# CAT-897-F.net
KiCad netlist of a schematic drawn in EAGLE
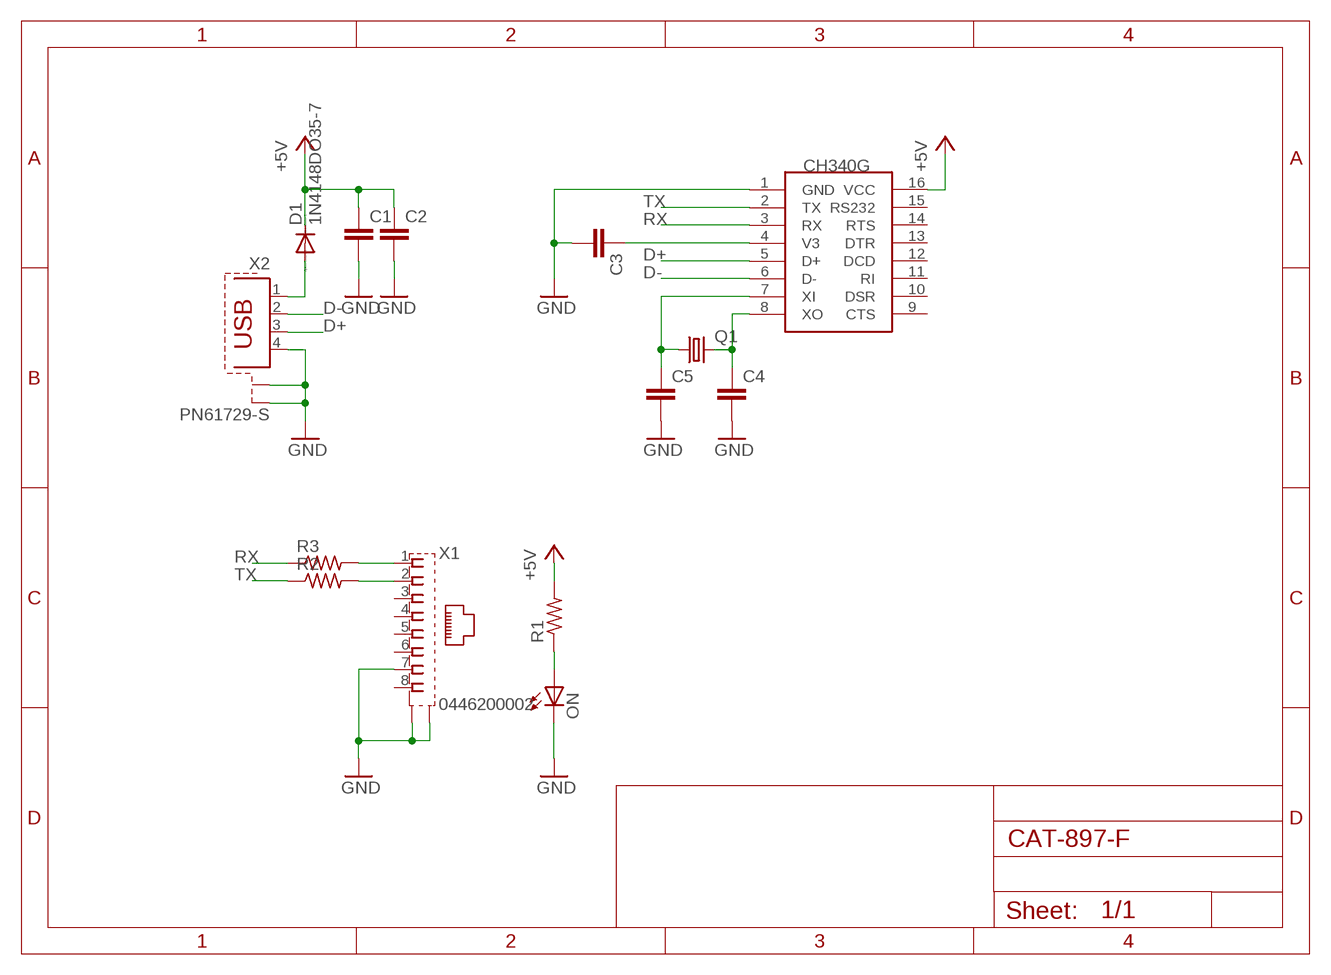
[diagram p0: schematic, sheet 1]

(export (version "E")
  (design (tool "Eeschema 10.0.6"))
  (components
    (comp (ref "C1")
      (value "C-EUC0805K")
      (footprint "eagle-import:C0805K")
      (libsource (lib "eagle-import") (part "C-EUC0805K"))
    )
    (comp (ref "C2")
      (value "C-EUC0805K")
      (footprint "eagle-import:C0805K")
      (libsource (lib "eagle-import") (part "C-EUC0805K"))
    )
    (comp (ref "C3")
      (value "C-EUC0805K")
      (footprint "eagle-import:C0805K")
      (libsource (lib "eagle-import") (part "C-EUC0805K"))
    )
    (comp (ref "C4")
      (value "C-EUC0805K")
      (footprint "eagle-import:C0805K")
      (libsource (lib "eagle-import") (part "C-EUC0805K"))
    )
    (comp (ref "C5")
      (value "C-EUC0805K")
      (footprint "eagle-import:C0805K")
      (libsource (lib "eagle-import") (part "C-EUC0805K"))
    )
    (comp (ref "D1")
      (value "1N4148DO35-7")
      (footprint "eagle-import:DO35-7")
      (libsource (lib "eagle-import") (part "1N4148DO35-7"))
    )
    (comp (ref "ON")
      (value "LED3MM")
      (footprint "eagle-import:LED3MM")
      (libsource (lib "eagle-import") (part "LED3MM"))
    )
    (comp (ref "Q1")
      (value "CRYSTALHC49S")
      (footprint "eagle-import:HC49_S")
      (libsource (lib "eagle-import") (part "CRYSTALHC49S"))
    )
    (comp (ref "R1")
      (value "R-US_R0805")
      (footprint "eagle-import:R0805")
      (libsource (lib "eagle-import") (part "R-US_R0805"))
    )
    (comp (ref "R2")
      (value "R-US_M0805")
      (footprint "eagle-import:M0805")
      (libsource (lib "eagle-import") (part "R-US_M0805"))
    )
    (comp (ref "R3")
      (value "R-US_M0805")
      (footprint "eagle-import:M0805")
      (libsource (lib "eagle-import") (part "R-US_M0805"))
    )
    (comp (ref "U$1")
      (value "CH340G")
      (footprint "eagle-import:SOIC16")
      (libsource (lib "eagle-import") (part "CH340G"))
    )
    (comp (ref "X1")
      (value "0446200002")
      (footprint "eagle-import:0446200002")
      (fields (field (name "MF") "MOLEX"))
      (libsource (lib "eagle-import") (part "0446200002"))
    )
    (comp (ref "X2")
      (value "PN61729-S")
      (footprint "eagle-import:PN61729-S")
      (libsource (lib "eagle-import") (part "PN61729-S"))
    )
  )
  (nets
    (net (code "1") (name "+5V") (class "Default")
      (node (ref "C1") (pin "1") (pinfunction "1_1") (pintype "passive"))
      (node (ref "C2") (pin "1") (pinfunction "1_1") (pintype "passive"))
      (node (ref "D1") (pin "C") (pinfunction "C_C") (pintype "passive"))
      (node (ref "R1") (pin "2") (pinfunction "2_2") (pintype "passive"))
      (node (ref "U$1") (pin "16") (pinfunction "VCC_16") (pintype "bidirectional"))
    )
    (net (code "2") (name "/D+") (class "Default")
      (node (ref "U$1") (pin "5") (pinfunction "D+_5") (pintype "bidirectional"))
      (node (ref "X2") (pin "3") (pinfunction "3_3") (pintype "passive"))
    )
    (net (code "3") (name "/D-") (class "Default")
      (node (ref "U$1") (pin "6") (pinfunction "D-_6") (pintype "bidirectional"))
      (node (ref "X2") (pin "2") (pinfunction "2_2") (pintype "passive"))
    )
    (net (code "4") (name "/RX") (class "Default")
      (node (ref "R3") (pin "1") (pinfunction "1_1") (pintype "passive"))
      (node (ref "U$1") (pin "3") (pinfunction "RX_3") (pintype "bidirectional"))
    )
    (net (code "5") (name "/TX") (class "Default")
      (node (ref "R2") (pin "1") (pinfunction "1_1") (pintype "passive"))
      (node (ref "U$1") (pin "2") (pinfunction "TX_2") (pintype "bidirectional"))
    )
    (net (code "6") (name "GND") (class "Default")
      (node (ref "C1") (pin "2") (pinfunction "2_2") (pintype "passive"))
      (node (ref "C2") (pin "2") (pinfunction "2_2") (pintype "passive"))
      (node (ref "C3") (pin "2") (pinfunction "2_2") (pintype "passive"))
      (node (ref "C4") (pin "2") (pinfunction "2_2") (pintype "passive"))
      (node (ref "C5") (pin "2") (pinfunction "2_2") (pintype "passive"))
      (node (ref "ON") (pin "K") (pinfunction "C_K") (pintype "passive"))
      (node (ref "U$1") (pin "1") (pinfunction "GND_1") (pintype "bidirectional"))
      (node (ref "X1") (pin "7") (pinfunction "7_7") (pintype "passive"))
      (node (ref "X1") (pin "S@1") (pinfunction "S1_S@1") (pintype "passive"))
      (node (ref "X1") (pin "S@2") (pinfunction "S2_S@2") (pintype "passive"))
      (node (ref "X2") (pin "4") (pinfunction "4_4") (pintype "passive"))
      (node (ref "X2") (pin "S1") (pinfunction "S1_S1") (pintype "passive"))
      (node (ref "X2") (pin "S2") (pinfunction "S2_S2") (pintype "passive"))
    )
    (net (code "7") (name "Net-(D1-PadA)") (class "Default")
      (node (ref "D1") (pin "A") (pinfunction "A_A") (pintype "passive"))
      (node (ref "X2") (pin "1") (pinfunction "1_1") (pintype "passive"))
    )
    (net (code "8") (name "Net-(ON-PadA)") (class "Default")
      (node (ref "ON") (pin "A") (pinfunction "A_A") (pintype "passive"))
      (node (ref "R1") (pin "1") (pinfunction "1_1") (pintype "passive"))
    )
    (net (code "9") (name "Net-(R2-Pad2)") (class "Default")
      (node (ref "R2") (pin "2") (pinfunction "2_2") (pintype "passive"))
      (node (ref "X1") (pin "2") (pinfunction "2_2") (pintype "passive"))
    )
    (net (code "10") (name "Net-(R3-Pad2)") (class "Default")
      (node (ref "R3") (pin "2") (pinfunction "2_2") (pintype "passive"))
      (node (ref "X1") (pin "1") (pinfunction "1_1") (pintype "passive"))
    )
    (net (code "11") (name "Net-(U$1-V3)") (class "Default")
      (node (ref "C3") (pin "1") (pinfunction "1_1") (pintype "passive"))
      (node (ref "U$1") (pin "4") (pinfunction "V3_4") (pintype "bidirectional"))
    )
    (net (code "12") (name "Net-(U$1-XI)") (class "Default")
      (node (ref "C5") (pin "1") (pinfunction "1_1") (pintype "passive"))
      (node (ref "Q1") (pin "1") (pinfunction "1_1") (pintype "passive"))
      (node (ref "U$1") (pin "7") (pinfunction "XI_7") (pintype "bidirectional"))
    )
    (net (code "13") (name "Net-(U$1-XO)") (class "Default")
      (node (ref "C4") (pin "1") (pinfunction "1_1") (pintype "passive"))
      (node (ref "Q1") (pin "2") (pinfunction "2_2") (pintype "passive"))
      (node (ref "U$1") (pin "8") (pinfunction "XO_8") (pintype "bidirectional"))
    )
    (net (code "14") (name "unconnected-(U$1-CTS-Pad9)") (class "Default")
      (node (ref "U$1") (pin "9") (pinfunction "CTS_9") (pintype "bidirectional"))
    )
    (net (code "15") (name "unconnected-(U$1-DCD-Pad12)") (class "Default")
      (node (ref "U$1") (pin "12") (pinfunction "DCD_12") (pintype "bidirectional"))
    )
    (net (code "16") (name "unconnected-(U$1-DSR-Pad10)") (class "Default")
      (node (ref "U$1") (pin "10") (pinfunction "DSR_10") (pintype "bidirectional"))
    )
    (net (code "17") (name "unconnected-(U$1-DTR-Pad13)") (class "Default")
      (node (ref "U$1") (pin "13") (pinfunction "DTR_13") (pintype "bidirectional"))
    )
    (net (code "18") (name "unconnected-(U$1-RI-Pad11)") (class "Default")
      (node (ref "U$1") (pin "11") (pinfunction "RI_11") (pintype "bidirectional"))
    )
    (net (code "19") (name "unconnected-(U$1-RS232-Pad15)") (class "Default")
      (node (ref "U$1") (pin "15") (pinfunction "RS232_15") (pintype "bidirectional"))
    )
    (net (code "20") (name "unconnected-(U$1-RTS-Pad14)") (class "Default")
      (node (ref "U$1") (pin "14") (pinfunction "RTS_14") (pintype "bidirectional"))
    )
    (net (code "21") (name "unconnected-(X1-Pad3)") (class "Default")
      (node (ref "X1") (pin "3") (pinfunction "3_3") (pintype "passive"))
    )
    (net (code "22") (name "unconnected-(X1-Pad4)") (class "Default")
      (node (ref "X1") (pin "4") (pinfunction "4_4") (pintype "passive"))
    )
    (net (code "23") (name "unconnected-(X1-Pad5)") (class "Default")
      (node (ref "X1") (pin "5") (pinfunction "5_5") (pintype "passive"))
    )
    (net (code "24") (name "unconnected-(X1-Pad6)") (class "Default")
      (node (ref "X1") (pin "6") (pinfunction "6_6") (pintype "passive"))
    )
    (net (code "25") (name "unconnected-(X1-Pad8)") (class "Default")
      (node (ref "X1") (pin "8") (pinfunction "8_8") (pintype "passive"))
    )
  )
)
